# MCU.net
KiCad netlist of a schematic drawn in Altium Designer
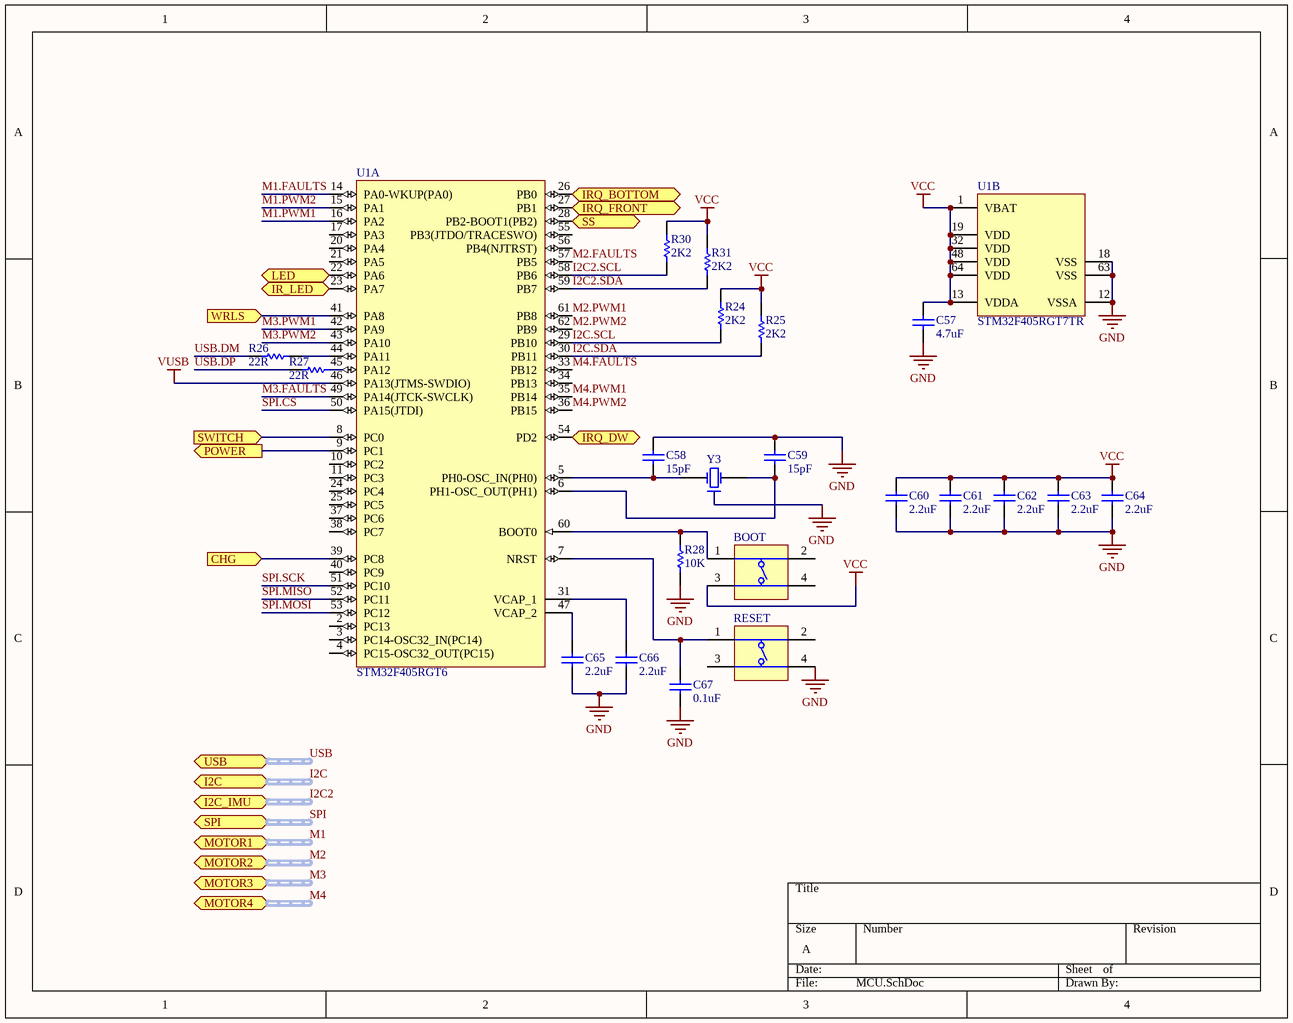
[diagram p0: MCU.SchDoc]

(export (version "E")
  (design (tool "Eeschema 10.0.6"))
  (components
    (comp (ref "BOOT")
      (value "~")
      (footprint "SWITCH")
      (description "Switch, SPNO Push Button SMD")
      (fields
        (field (name "MANUFACTURER") "C&K Components")
        (field (name "PARTNUMBER") "PTS810 SJM 250 SMTR LFS")
      )
      (libsource (lib "Components") (part "DIPT-DTSM-6"))
    )
    (comp (ref "C57")
      (value "4.7uF")
      (footprint "C0402[1005X55]")
      (description "4.7uF 6.3V 20% 0402 (1005 Metric)")
      (fields (field (name "TOLERANCE") "20%") (field (name "PARTNUMBER") "GRM155R60J475ME47D"))
      (libsource (lib "Capacitors") (part "CAP_4.7uF_6.3V_0402_20%"))
    )
    (comp (ref "C58")
      (value "15pF")
      (footprint "C0402[1005X55]")
      (description "15pF 50V 5% 0402 (1005 Metric)")
      (fields (field (name "TOLERANCE") "5%") (field (name "PARTNUMBER") "GRM1555C1H150JA01D"))
      (libsource (lib "Capacitors") (part "CAP_15pF_50V_0402_5%"))
    )
    (comp (ref "C59")
      (value "15pF")
      (footprint "C0402[1005X55]")
      (description "15pF 50V 5% 0402 (1005 Metric)")
      (fields (field (name "TOLERANCE") "5%") (field (name "PARTNUMBER") "GRM1555C1H150JA01D"))
      (libsource (lib "Capacitors") (part "CAP_15pF_50V_0402_5%"))
    )
    (comp (ref "C60")
      (value "2.2uF")
      (footprint "C0402[1005X55]")
      (description "2.2uF 6.3V 20% 0402 (1005 Metric)")
      (fields (field (name "TOLERANCE") "20%") (field (name "PARTNUMBER") "GRM155R60J225ME15D"))
      (libsource (lib "Capacitors") (part "CAP_2.2uF_6.3V_0402_20%"))
    )
    (comp (ref "C61")
      (value "2.2uF")
      (footprint "C0402[1005X55]")
      (description "2.2uF 6.3V 20% 0402 (1005 Metric)")
      (fields (field (name "TOLERANCE") "20%") (field (name "PARTNUMBER") "GRM155R60J225ME15D"))
      (libsource (lib "Capacitors") (part "CAP_2.2uF_6.3V_0402_20%"))
    )
    (comp (ref "C62")
      (value "2.2uF")
      (footprint "C0402[1005X55]")
      (description "2.2uF 6.3V 20% 0402 (1005 Metric)")
      (fields (field (name "TOLERANCE") "20%") (field (name "PARTNUMBER") "GRM155R60J225ME15D"))
      (libsource (lib "Capacitors") (part "CAP_2.2uF_6.3V_0402_20%"))
    )
    (comp (ref "C63")
      (value "2.2uF")
      (footprint "C0402[1005X55]")
      (description "2.2uF 6.3V 20% 0402 (1005 Metric)")
      (fields (field (name "TOLERANCE") "20%") (field (name "PARTNUMBER") "GRM155R60J225ME15D"))
      (libsource (lib "Capacitors") (part "CAP_2.2uF_6.3V_0402_20%"))
    )
    (comp (ref "C64")
      (value "2.2uF")
      (footprint "C0402[1005X55]")
      (description "2.2uF 6.3V 20% 0402 (1005 Metric)")
      (fields (field (name "TOLERANCE") "20%") (field (name "PARTNUMBER") "GRM155R60J225ME15D"))
      (libsource (lib "Capacitors") (part "CAP_2.2uF_6.3V_0402_20%"))
    )
    (comp (ref "C65")
      (value "2.2uF")
      (footprint "C0402[1005X55]")
      (description "2.2uF 6.3V 20% 0402 (1005 Metric)")
      (fields (field (name "TOLERANCE") "20%") (field (name "PARTNUMBER") "GRM155R60J225ME15D"))
      (libsource (lib "Capacitors") (part "CAP_2.2uF_6.3V_0402_20%"))
    )
    (comp (ref "C66")
      (value "2.2uF")
      (footprint "C0402[1005X55]")
      (description "2.2uF 6.3V 20% 0402 (1005 Metric)")
      (fields (field (name "TOLERANCE") "20%") (field (name "PARTNUMBER") "GRM155R60J225ME15D"))
      (libsource (lib "Capacitors") (part "CAP_2.2uF_6.3V_0402_20%"))
    )
    (comp (ref "C67")
      (value "0.1uF")
      (footprint "C0402[1005X55]")
      (description "0.1uF 6.3V 10% 0402 (1005 Metric)")
      (fields (field (name "TOLERANCE") "10%") (field (name "PARTNUMBER") "GRM155R70J104KA01D"))
      (libsource (lib "Capacitors") (part "CAP_0.1uF_6.3V_0402_10%"))
    )
    (comp (ref "R24")
      (value "2K2")
      (footprint "R0402[1005]")
      (description "2K2 0.063W 1% 0402 (1005 Metric)")
      (fields (field (name "TOLERANCE") "1%") (field (name "POWER") "0.063W"))
      (libsource (lib "Resistors") (part "RES_2K2_0402_1%"))
    )
    (comp (ref "R25")
      (value "2K2")
      (footprint "R0402[1005]")
      (description "2K2 0.063W 1% 0402 (1005 Metric)")
      (fields (field (name "TOLERANCE") "1%") (field (name "POWER") "0.063W"))
      (libsource (lib "Resistors") (part "RES_2K2_0402_1%"))
    )
    (comp (ref "R26")
      (value "22R")
      (footprint "R0402[1005]")
      (description "22R 0.063W 1% 0402 (1005 Metric)")
      (fields (field (name "POWER") "0.063W") (field (name "TOLERANCE") "1%"))
      (libsource (lib "Resistors") (part "RES_22R_0402_1%"))
    )
    (comp (ref "R27")
      (value "22R")
      (footprint "R0402[1005]")
      (description "22R 0.063W 1% 0402 (1005 Metric)")
      (fields (field (name "POWER") "0.063W") (field (name "TOLERANCE") "1%"))
      (libsource (lib "Resistors") (part "RES_22R_0402_1%"))
    )
    (comp (ref "R28")
      (value "10K")
      (footprint "R0402[1005]")
      (description "10K 0.063W 1% 0402 (1005 Metric)")
      (fields (field (name "TOLERANCE") "1%") (field (name "POWER") "0.063W"))
      (libsource (lib "Resistors") (part "RES_10K_0402_1%"))
    )
    (comp (ref "R30")
      (value "2K2")
      (footprint "R0402[1005]")
      (description "2K2 0.063W 1% 0402 (1005 Metric)")
      (fields (field (name "TOLERANCE") "1%") (field (name "POWER") "0.063W"))
      (libsource (lib "Resistors") (part "RES_2K2_0402_1%"))
    )
    (comp (ref "R31")
      (value "2K2")
      (footprint "R0402[1005]")
      (description "2K2 0.063W 1% 0402 (1005 Metric)")
      (fields (field (name "TOLERANCE") "1%") (field (name "POWER") "0.063W"))
      (libsource (lib "Resistors") (part "RES_2K2_0402_1%"))
    )
    (comp (ref "RESET")
      (value "~")
      (footprint "SWITCH")
      (description "Switch, SPNO Push Button SMD")
      (fields
        (field (name "MANUFACTURER") "C&K Components")
        (field (name "PARTNUMBER") "PTS810 SJM 250 SMTR LFS")
      )
      (libsource (lib "Components") (part "DIPT-DTSM-6"))
    )
    (comp (ref "U1")
      (value "STM32F405RGT7TR")
      (footprint "STM-LQFP64_V")
      (fields (field (name "MANUFACTURER") "STMicroelectronics"))
      (libsource (lib "Altium Content Vault") (part "CMP-0243-00089-2"))
    )
    (comp (ref "Y3")
      (value "~")
      (footprint "ABRA-ABM3B-4_V")
      (fields (field (name "PARTNUMBER") "ABM3B-8.000MHZ-10-1UT") (field (name "MANUFACTURER") "ABRACON"))
      (libsource (lib "Components") (part "ABRA-ABM3B-4"))
    )
  )
  (nets
    (net (code "9") (name "/CHG") (class "Default")
      (node (ref "U1") (pin "39") (pinfunction "PC8_39") (pintype "bidirectional"))
    )
    (net (code "10") (name "/I2C.SCL") (class "Default")
      (node (ref "R24") (pin "1") (pinfunction "1_1") (pintype "passive"))
      (node (ref "U1") (pin "29") (pinfunction "PB10_29") (pintype "bidirectional"))
    )
    (net (code "11") (name "/I2C.SDA") (class "Default")
      (node (ref "R25") (pin "1") (pinfunction "1_1") (pintype "passive"))
      (node (ref "U1") (pin "30") (pinfunction "PB11_30") (pintype "bidirectional"))
    )
    (net (code "12") (name "/I2C2.SCL") (class "Default")
      (node (ref "R30") (pin "1") (pinfunction "1_1") (pintype "passive"))
      (node (ref "U1") (pin "58") (pinfunction "PB6_58") (pintype "bidirectional"))
    )
    (net (code "13") (name "/I2C2.SDA") (class "Default")
      (node (ref "R31") (pin "1") (pinfunction "1_1") (pintype "passive"))
      (node (ref "U1") (pin "59") (pinfunction "PB7_59") (pintype "bidirectional"))
    )
    (net (code "14") (name "/IRQ_BOTTOM") (class "Default")
      (node (ref "U1") (pin "26") (pinfunction "PB0_26") (pintype "bidirectional"))
    )
    (net (code "15") (name "/IRQ_DW") (class "Default")
      (node (ref "U1") (pin "54") (pinfunction "PD2_54") (pintype "bidirectional"))
    )
    (net (code "16") (name "/IRQ_FRONT") (class "Default")
      (node (ref "U1") (pin "27") (pinfunction "PB1_27") (pintype "bidirectional"))
    )
    (net (code "17") (name "/IR_LED") (class "Default")
      (node (ref "U1") (pin "23") (pinfunction "PA7_23") (pintype "bidirectional"))
    )
    (net (code "18") (name "/LED") (class "Default")
      (node (ref "U1") (pin "22") (pinfunction "PA6_22") (pintype "bidirectional"))
    )
    (net (code "19") (name "/M1.FAULTS") (class "Default")
      (node (ref "U1") (pin "14") (pinfunction "PA0-WKUP(PA0)_14") (pintype "bidirectional"))
    )
    (net (code "20") (name "/M1.PWM1") (class "Default")
      (node (ref "U1") (pin "16") (pinfunction "PA2_16") (pintype "bidirectional"))
    )
    (net (code "21") (name "/M1.PWM2") (class "Default")
      (node (ref "U1") (pin "15") (pinfunction "PA1_15") (pintype "bidirectional"))
    )
    (net (code "22") (name "/M2.FAULTS") (class "Default")
      (node (ref "U1") (pin "57") (pinfunction "PB5_57") (pintype "bidirectional"))
    )
    (net (code "23") (name "/M2.PWM1") (class "Default")
      (node (ref "U1") (pin "61") (pinfunction "PB8_61") (pintype "bidirectional"))
    )
    (net (code "24") (name "/M2.PWM2") (class "Default")
      (node (ref "U1") (pin "62") (pinfunction "PB9_62") (pintype "bidirectional"))
    )
    (net (code "25") (name "/M3.FAULTS") (class "Default")
      (node (ref "U1") (pin "49") (pinfunction "PA14(JTCK-SWCLK)_49") (pintype "bidirectional"))
    )
    (net (code "26") (name "/M3.PWM1") (class "Default")
      (node (ref "U1") (pin "42") (pinfunction "PA9_42") (pintype "bidirectional"))
    )
    (net (code "27") (name "/M3.PWM2") (class "Default")
      (node (ref "U1") (pin "43") (pinfunction "PA10_43") (pintype "bidirectional"))
    )
    (net (code "28") (name "/M4.FAULTS") (class "Default")
      (node (ref "U1") (pin "33") (pinfunction "PB12_33") (pintype "bidirectional"))
    )
    (net (code "29") (name "/M4.PWM1") (class "Default")
      (node (ref "U1") (pin "35") (pinfunction "PB14_35") (pintype "bidirectional"))
    )
    (net (code "30") (name "/M4.PWM2") (class "Default")
      (node (ref "U1") (pin "36") (pinfunction "PB15_36") (pintype "bidirectional"))
    )
    (net (code "31") (name "/POWER") (class "Default")
      (node (ref "U1") (pin "9") (pinfunction "PC1_9") (pintype "bidirectional"))
    )
    (net (code "32") (name "/SPI.CS") (class "Default")
      (node (ref "U1") (pin "50") (pinfunction "PA15(JTDI)_50") (pintype "bidirectional"))
    )
    (net (code "33") (name "/SPI.MISO") (class "Default")
      (node (ref "U1") (pin "52") (pinfunction "PC11_52") (pintype "bidirectional"))
    )
    (net (code "34") (name "/SPI.MOSI") (class "Default")
      (node (ref "U1") (pin "53") (pinfunction "PC12_53") (pintype "bidirectional"))
    )
    (net (code "35") (name "/SPI.SCK") (class "Default")
      (node (ref "U1") (pin "51") (pinfunction "PC10_51") (pintype "bidirectional"))
    )
    (net (code "36") (name "/SS") (class "Default")
      (node (ref "U1") (pin "28") (pinfunction "PB2-BOOT1(PB2)_28") (pintype "bidirectional"))
    )
    (net (code "37") (name "/SWITCH") (class "Default")
      (node (ref "U1") (pin "8") (pinfunction "PC0_8") (pintype "bidirectional"))
    )
    (net (code "38") (name "/USB.DM") (class "Default")
      (node (ref "R26") (pin "1") (pinfunction "1_1") (pintype "passive"))
    )
    (net (code "39") (name "/USB.DP") (class "Default")
      (node (ref "R27") (pin "1") (pinfunction "1_1") (pintype "passive"))
    )
    (net (code "40") (name "/WRLS") (class "Default")
      (node (ref "U1") (pin "41") (pinfunction "PA8_41") (pintype "bidirectional"))
    )
    (net (code "49") (name "GND") (class "Default")
      (node (ref "C57") (pin "1") (pinfunction "1_1") (pintype "passive"))
      (node (ref "C58") (pin "2") (pinfunction "2_2") (pintype "passive"))
      (node (ref "C59") (pin "2") (pinfunction "2_2") (pintype "passive"))
      (node (ref "C60") (pin "1") (pinfunction "1_1") (pintype "passive"))
      (node (ref "C61") (pin "1") (pinfunction "1_1") (pintype "passive"))
      (node (ref "C62") (pin "1") (pinfunction "1_1") (pintype "passive"))
      (node (ref "C63") (pin "1") (pinfunction "1_1") (pintype "passive"))
      (node (ref "C64") (pin "1") (pinfunction "1_1") (pintype "passive"))
      (node (ref "C65") (pin "1") (pinfunction "1_1") (pintype "passive"))
      (node (ref "C66") (pin "1") (pinfunction "1_1") (pintype "passive"))
      (node (ref "C67") (pin "1") (pinfunction "1_1") (pintype "passive"))
      (node (ref "R28") (pin "1") (pinfunction "1_1") (pintype "passive"))
      (node (ref "RESET") (pin "4") (pinfunction "T3_4") (pintype "passive"))
      (node (ref "U1") (pin "12") (pinfunction "VSSA_12") (pintype "power_in"))
      (node (ref "U1") (pin "18") (pinfunction "VSS_18") (pintype "power_in"))
      (node (ref "U1") (pin "63") (pinfunction "VSS_63") (pintype "power_in"))
      (node (ref "Y3") (pin "2") (pinfunction "2_2") (pintype "passive"))
    )
    (net (code "50") (name "Net-(BOOT-T1)") (class "Default")
      (node (ref "BOOT") (pin "1") (pinfunction "T1_1") (pintype "passive"))
      (node (ref "R28") (pin "2") (pinfunction "2_2") (pintype "passive"))
      (node (ref "U1") (pin "60") (pinfunction "BOOT0_60") (pintype "input"))
    )
    (net (code "51") (name "Net-(RESET-T1)") (class "Default")
      (node (ref "C67") (pin "2") (pinfunction "2_2") (pintype "passive"))
      (node (ref "RESET") (pin "1") (pinfunction "T1_1") (pintype "passive"))
      (node (ref "U1") (pin "7") (pinfunction "NRST_7") (pintype "bidirectional"))
    )
    (net (code "52") (name "Net-(U1A-PA11)") (class "Default")
      (node (ref "R26") (pin "2") (pinfunction "2_2") (pintype "passive"))
      (node (ref "U1") (pin "44") (pinfunction "PA11_44") (pintype "bidirectional"))
    )
    (net (code "53") (name "Net-(U1A-PA12)") (class "Default")
      (node (ref "R27") (pin "2") (pinfunction "2_2") (pintype "passive"))
      (node (ref "U1") (pin "45") (pinfunction "PA12_45") (pintype "bidirectional"))
    )
    (net (code "54") (name "Net-(U1A-PH0-OSC_IN(PH0))") (class "Default")
      (node (ref "C58") (pin "1") (pinfunction "1_1") (pintype "passive"))
      (node (ref "U1") (pin "5") (pinfunction "PH0-OSC_IN(PH0)_5") (pintype "bidirectional"))
      (node (ref "Y3") (pin "3") (pinfunction "X2_3") (pintype "passive"))
    )
    (net (code "55") (name "Net-(U1A-PH1-OSC_OUT(PH1))") (class "Default")
      (node (ref "C59") (pin "1") (pinfunction "1_1") (pintype "passive"))
      (node (ref "U1") (pin "6") (pinfunction "PH1-OSC_OUT(PH1)_6") (pintype "bidirectional"))
      (node (ref "Y3") (pin "1") (pinfunction "X1_1") (pintype "passive"))
    )
    (net (code "56") (name "Net-(U1A-VCAP_1)") (class "Default")
      (node (ref "C66") (pin "2") (pinfunction "2_2") (pintype "passive"))
      (node (ref "U1") (pin "31") (pinfunction "VCAP_1_31") (pintype "power_in"))
    )
    (net (code "57") (name "Net-(U1A-VCAP_2)") (class "Default")
      (node (ref "C65") (pin "2") (pinfunction "2_2") (pintype "passive"))
      (node (ref "U1") (pin "47") (pinfunction "VCAP_2_47") (pintype "power_in"))
    )
    (net (code "58") (name "VCC") (class "Default")
      (node (ref "BOOT") (pin "3") (pinfunction "T3_3") (pintype "passive"))
      (node (ref "C57") (pin "2") (pinfunction "2_2") (pintype "passive"))
      (node (ref "C60") (pin "2") (pinfunction "2_2") (pintype "passive"))
      (node (ref "C61") (pin "2") (pinfunction "2_2") (pintype "passive"))
      (node (ref "C62") (pin "2") (pinfunction "2_2") (pintype "passive"))
      (node (ref "C63") (pin "2") (pinfunction "2_2") (pintype "passive"))
      (node (ref "C64") (pin "2") (pinfunction "2_2") (pintype "passive"))
      (node (ref "R24") (pin "2") (pinfunction "2_2") (pintype "passive"))
      (node (ref "R25") (pin "2") (pinfunction "2_2") (pintype "passive"))
      (node (ref "R30") (pin "2") (pinfunction "2_2") (pintype "passive"))
      (node (ref "R31") (pin "2") (pinfunction "2_2") (pintype "passive"))
      (node (ref "U1") (pin "1") (pinfunction "VBAT_1") (pintype "power_in"))
      (node (ref "U1") (pin "13") (pinfunction "VDDA_13") (pintype "power_in"))
      (node (ref "U1") (pin "19") (pinfunction "VDD_19") (pintype "power_in"))
      (node (ref "U1") (pin "32") (pinfunction "VDD_32") (pintype "power_in"))
      (node (ref "U1") (pin "48") (pinfunction "VDD_48") (pintype "power_in"))
      (node (ref "U1") (pin "64") (pinfunction "VDD_64") (pintype "power_in"))
    )
    (net (code "59") (name "VUSB") (class "Default")
      (node (ref "U1") (pin "46") (pinfunction "PA13(JTMS-SWDIO)_46") (pintype "bidirectional"))
    )
    (net (code "60") (name "unconnected-(BOOT-T2-Pad2)") (class "Default")
      (node (ref "BOOT") (pin "2") (pinfunction "T2_2") (pintype "passive"))
    )
    (net (code "61") (name "unconnected-(BOOT-T3-Pad4)") (class "Default")
      (node (ref "BOOT") (pin "4") (pinfunction "T3_4") (pintype "passive"))
    )
    (net (code "62") (name "unconnected-(RESET-T2-Pad2)") (class "Default")
      (node (ref "RESET") (pin "2") (pinfunction "T2_2") (pintype "passive"))
    )
    (net (code "63") (name "unconnected-(RESET-T3-Pad3)") (class "Default")
      (node (ref "RESET") (pin "3") (pinfunction "T3_3") (pintype "passive"))
    )
    (net (code "64") (name "unconnected-(U1A-PA3-Pad17)") (class "Default")
      (node (ref "U1") (pin "17") (pinfunction "PA3_17") (pintype "bidirectional"))
    )
    (net (code "65") (name "unconnected-(U1A-PA4-Pad20)") (class "Default")
      (node (ref "U1") (pin "20") (pinfunction "PA4_20") (pintype "bidirectional"))
    )
    (net (code "66") (name "unconnected-(U1A-PA5-Pad21)") (class "Default")
      (node (ref "U1") (pin "21") (pinfunction "PA5_21") (pintype "bidirectional"))
    )
    (net (code "67") (name "unconnected-(U1A-PB3(JTDO{slash}TRACESWO)-Pad55)") (class "Default")
      (node (ref "U1") (pin "55") (pinfunction "PB3(JTDO/TRACESWO)_55") (pintype "bidirectional"))
    )
    (net (code "68") (name "unconnected-(U1A-PB4(NJTRST)-Pad56)") (class "Default")
      (node (ref "U1") (pin "56") (pinfunction "PB4(NJTRST)_56") (pintype "bidirectional"))
    )
    (net (code "69") (name "unconnected-(U1A-PB13-Pad34)") (class "Default")
      (node (ref "U1") (pin "34") (pinfunction "PB13_34") (pintype "bidirectional"))
    )
    (net (code "70") (name "unconnected-(U1A-PC2-Pad10)") (class "Default")
      (node (ref "U1") (pin "10") (pinfunction "PC2_10") (pintype "bidirectional"))
    )
    (net (code "71") (name "unconnected-(U1A-PC3-Pad11)") (class "Default")
      (node (ref "U1") (pin "11") (pinfunction "PC3_11") (pintype "bidirectional"))
    )
    (net (code "72") (name "unconnected-(U1A-PC4-Pad24)") (class "Default")
      (node (ref "U1") (pin "24") (pinfunction "PC4_24") (pintype "bidirectional"))
    )
    (net (code "73") (name "unconnected-(U1A-PC5-Pad25)") (class "Default")
      (node (ref "U1") (pin "25") (pinfunction "PC5_25") (pintype "bidirectional"))
    )
    (net (code "74") (name "unconnected-(U1A-PC6-Pad37)") (class "Default")
      (node (ref "U1") (pin "37") (pinfunction "PC6_37") (pintype "bidirectional"))
    )
    (net (code "75") (name "unconnected-(U1A-PC7-Pad38)") (class "Default")
      (node (ref "U1") (pin "38") (pinfunction "PC7_38") (pintype "bidirectional"))
    )
    (net (code "76") (name "unconnected-(U1A-PC9-Pad40)") (class "Default")
      (node (ref "U1") (pin "40") (pinfunction "PC9_40") (pintype "bidirectional"))
    )
    (net (code "77") (name "unconnected-(U1A-PC13-Pad2)") (class "Default")
      (node (ref "U1") (pin "2") (pinfunction "PC13_2") (pintype "bidirectional"))
    )
    (net (code "78") (name "unconnected-(U1A-PC14-OSC32_IN(PC14)-Pad3)") (class "Default")
      (node (ref "U1") (pin "3") (pinfunction "PC14-OSC32_IN(PC14)_3") (pintype "bidirectional"))
    )
    (net (code "79") (name "unconnected-(U1A-PC15-OSC32_OUT(PC15)-Pad4)") (class "Default")
      (node (ref "U1") (pin "4") (pinfunction "PC15-OSC32_OUT(PC15)_4") (pintype "bidirectional"))
    )
  )
)
